# FE_Channel.net
KiCad netlist of a schematic drawn in Altium Designer
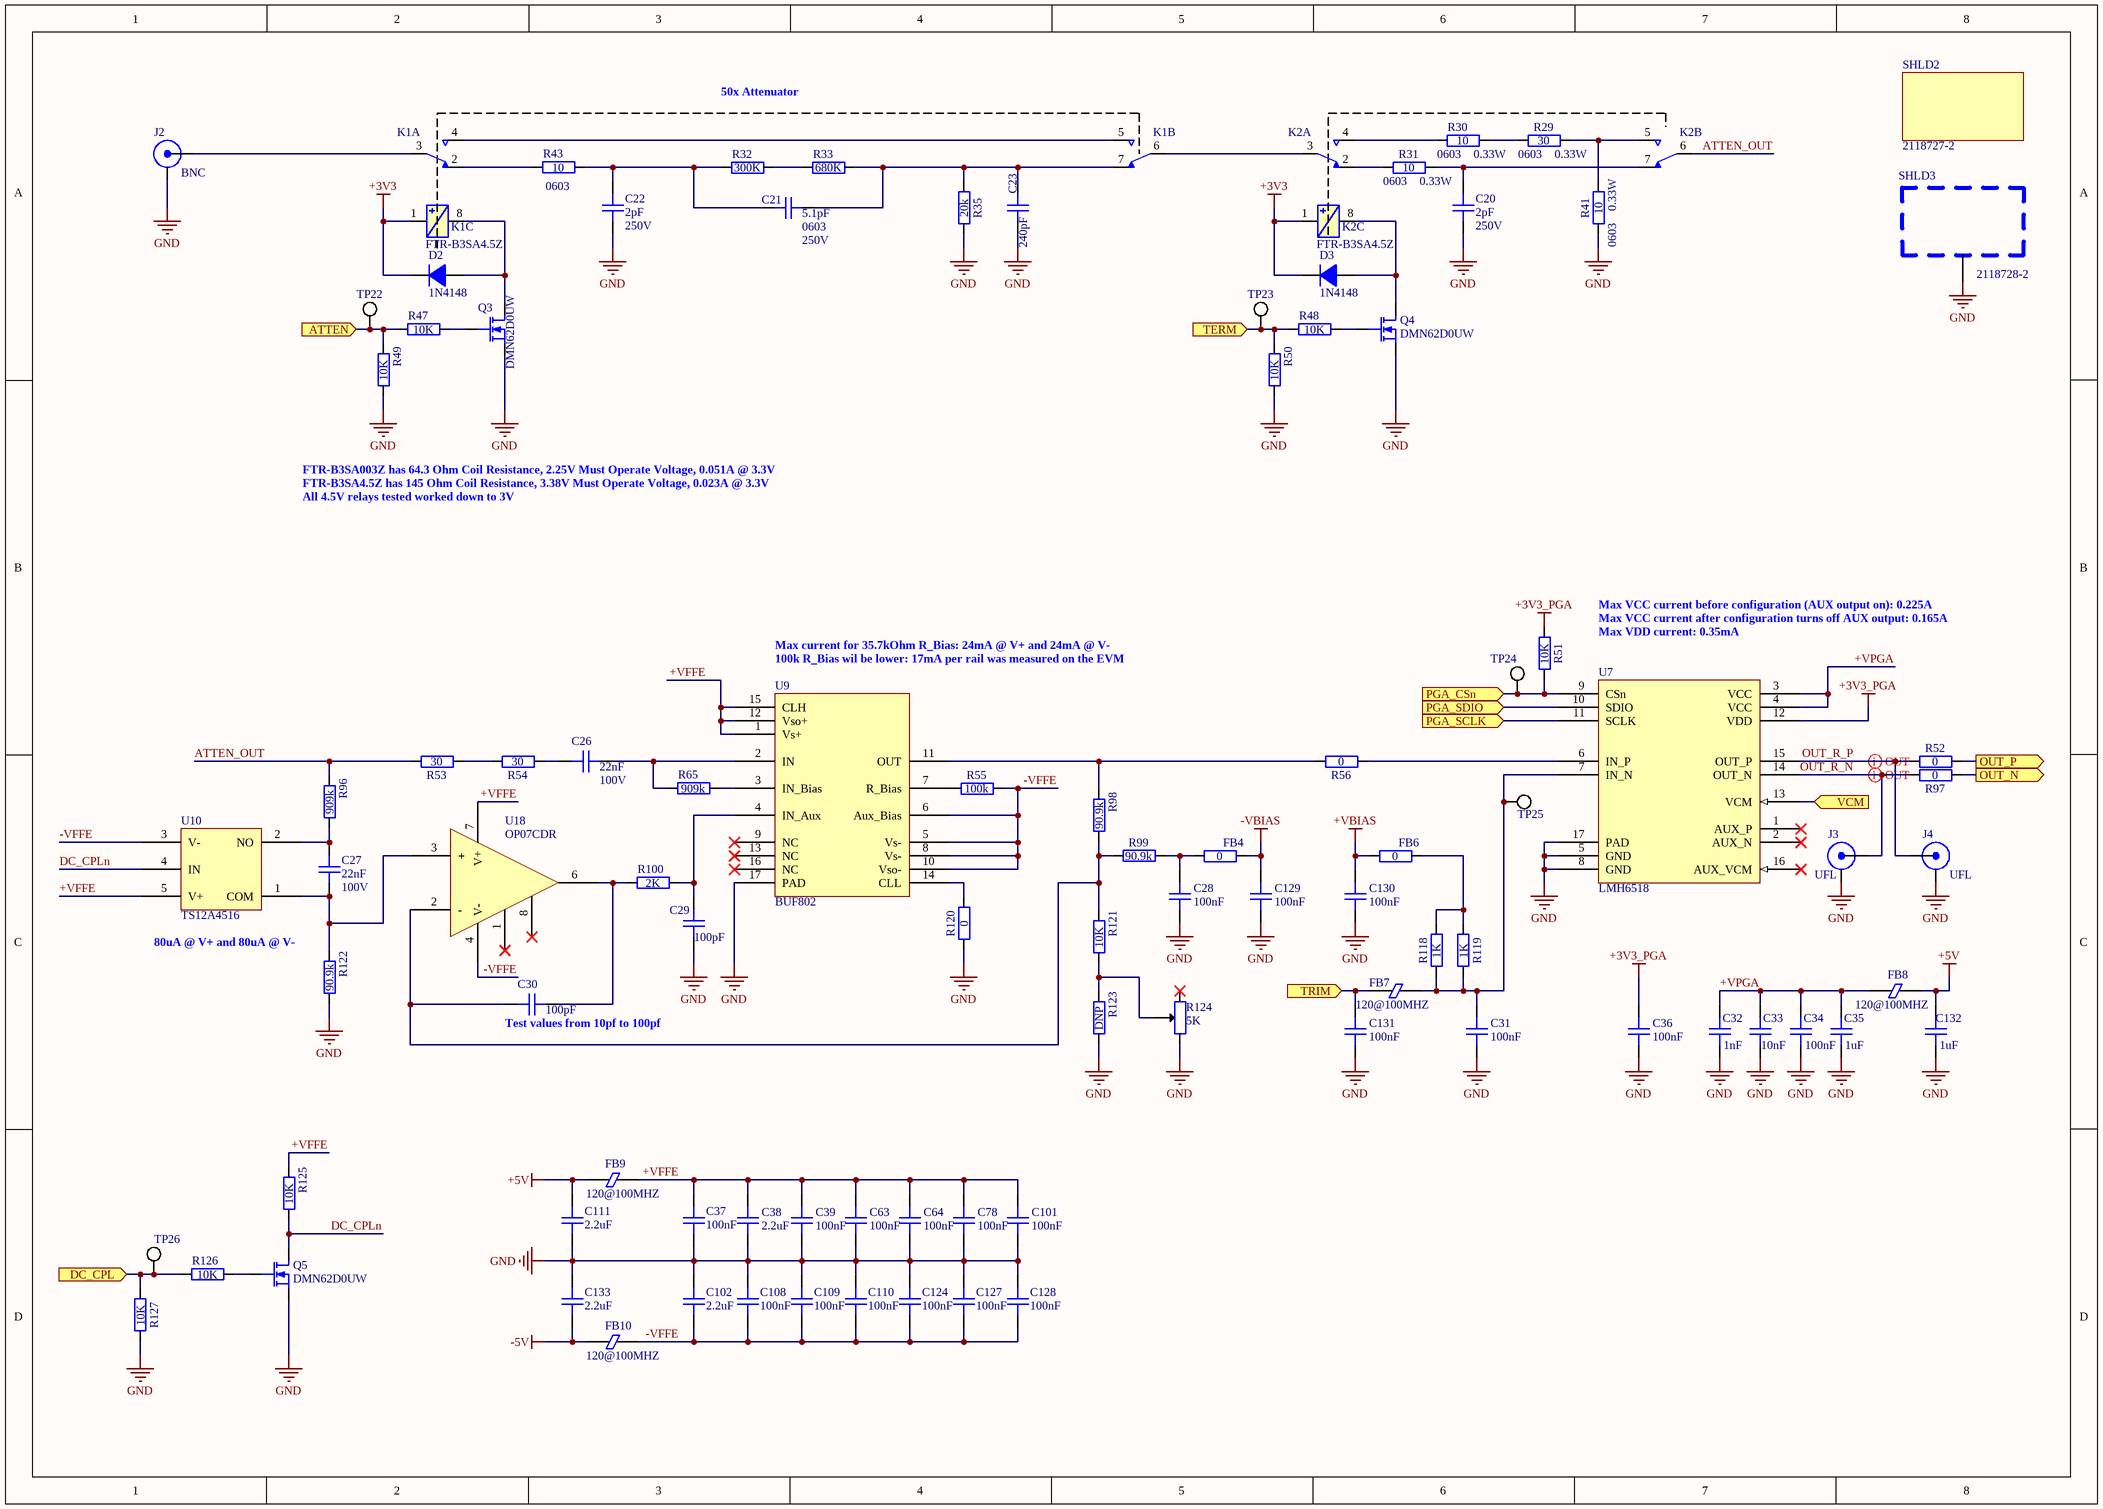
[diagram p0: FE_Channel.SchDoc]

(export (version "E")
  (design (tool "Eeschema 10.0.6"))
  (components
    (comp (ref "C20")
      (value "2pF")
      (footprint "GEN_C_0603")
      (fields
        (field (name "MANUFACTURER") "KEMET")
        (field (name "MANUFACTURER PART NUMBER") "CBR06C309BAGAC")
        (field (name "VOLTAGE RATING") "250V")
      )
      (libsource (lib "DSO") (part "CAP 2pF 250V C0G 0603"))
    )
    (comp (ref "C21")
      (value "5.1pF")
      (footprint "GEN_C_0603")
      (fields
        (field (name "PACKAGE") "0603")
        (field (name "VOLTAGE RATING") "250V")
        (field (name "MANUFACTURER") "KEMET")
        (field (name "MANUFACTURER PART NUMBER") "CBR06C519BAGAC")
      )
      (libsource (lib "DSO") (part "CAP 5.1pF 250V C0G 0603"))
    )
    (comp (ref "C22")
      (value "2pF")
      (footprint "GEN_C_0603")
      (fields
        (field (name "MANUFACTURER") "KEMET")
        (field (name "MANUFACTURER PART NUMBER") "CBR06C309BAGAC")
        (field (name "VOLTAGE RATING") "250V")
      )
      (libsource (lib "DSO") (part "CAP 2pF 250V C0G 0603"))
    )
    (comp (ref "C23")
      (value "240pF")
      (footprint "GEN_C_0805")
      (fields
        (field (name "MANUFACTURER") "Kyocera AVX")
        (field (name "MANUFACTURER PART NUMBER") "600F241FT250XT")
      )
      (libsource (lib "DSO") (part "CAP 240pF 250V C0G 0805"))
    )
    (comp (ref "C26")
      (value "22nF")
      (footprint "GEN_C_0603")
      (fields (field (name "VOLTAGE RATING") "100V"))
      (libsource (lib "DSO") (part "CAP 22nF 100V X7R 0603"))
    )
    (comp (ref "C27")
      (value "22nF")
      (footprint "GEN_C_0603")
      (fields (field (name "VOLTAGE RATING") "100V"))
      (libsource (lib "DSO") (part "CAP 22nF 100V X7R 0603"))
    )
    (comp (ref "C28")
      (value "100nF")
      (footprint "GEN_C_0402")
      (libsource (lib "DSO") (part "CAP 100nF 16V X7R 0402"))
    )
    (comp (ref "C29")
      (value "100pF")
      (footprint "GEN_C_0402")
      (libsource (lib "DSO") (part "CAP 100pF 50V C0G 0402"))
    )
    (comp (ref "C30")
      (value "100pF")
      (footprint "GEN_C_0402")
      (libsource (lib "DSO") (part "CAP 100pF 50V C0G 0402"))
    )
    (comp (ref "C31")
      (value "100nF")
      (footprint "GEN_C_0402")
      (libsource (lib "DSO") (part "CAP 100nF 16V X7R 0402"))
    )
    (comp (ref "C32")
      (value "1nF")
      (footprint "GEN_C_0402")
      (libsource (lib "DSO") (part "CAP 1nF 50V C0G 0402"))
    )
    (comp (ref "C33")
      (value "10nF")
      (footprint "GEN_C_0402")
      (libsource (lib "DSO") (part "CAP 10nF 50V X7R 0402"))
    )
    (comp (ref "C34")
      (value "100nF")
      (footprint "GEN_C_0402")
      (libsource (lib "DSO") (part "CAP 100nF 16V X7R 0402"))
    )
    (comp (ref "C35")
      (value "1uF")
      (footprint "GEN_C_0402")
      (libsource (lib "DSO") (part "CAP 1uF 25V X5R 0402"))
    )
    (comp (ref "C36")
      (value "100nF")
      (footprint "GEN_C_0402")
      (libsource (lib "DSO") (part "CAP 100nF 16V X7R 0402"))
    )
    (comp (ref "C37")
      (value "100nF")
      (footprint "GEN_C_0402")
      (fields
        (field (name "MANUFACTURER") "Murata")
        (field (name "HOUSE PART NUMBER") "C-100nF-0402-002")
        (field (name "MANUFACTURER PART NUMBER") "GCM155R71C104KA55D")
      )
      (libsource (lib "DSO") (part "CAP 100nF 16V X7R 0402"))
    )
    (comp (ref "C38")
      (value "2.2uF")
      (footprint "GEN_C_0402")
      (fields
        (field (name "MANUFACTURER") "Taiyo Yuden")
        (field (name "MANUFACTURER PART NUMBER") "LMK105BJ225MV-F")
      )
      (libsource (lib "DSO") (part "CAP 2.2uF 10V X5R 0402"))
    )
    (comp (ref "C39")
      (value "100nF")
      (footprint "GEN_C_0402")
      (libsource (lib "DSO") (part "CAP 100nF 16V X7R 0402"))
    )
    (comp (ref "C63")
      (value "100nF")
      (footprint "GEN_C_0402")
      (libsource (lib "DSO") (part "CAP 100nF 16V X7R 0402"))
    )
    (comp (ref "C64")
      (value "100nF")
      (footprint "GEN_C_0402")
      (libsource (lib "DSO") (part "CAP 100nF 16V X7R 0402"))
    )
    (comp (ref "C78")
      (value "100nF")
      (footprint "GEN_C_0402")
      (libsource (lib "DSO") (part "CAP 100nF 16V X7R 0402"))
    )
    (comp (ref "C101")
      (value "100nF")
      (footprint "GEN_C_0402")
      (libsource (lib "DSO") (part "CAP 100nF 16V X7R 0402"))
    )
    (comp (ref "C102")
      (value "2.2uF")
      (footprint "GEN_C_0402")
      (libsource (lib "DSO") (part "CAP 2.2uF 10V X5R 0402"))
    )
    (comp (ref "C108")
      (value "100nF")
      (footprint "GEN_C_0402")
      (libsource (lib "DSO") (part "CAP 100nF 16V X7R 0402"))
    )
    (comp (ref "C109")
      (value "100nF")
      (footprint "GEN_C_0402")
      (libsource (lib "DSO") (part "CAP 100nF 16V X7R 0402"))
    )
    (comp (ref "C110")
      (value "100nF")
      (footprint "GEN_C_0402")
      (libsource (lib "DSO") (part "CAP 100nF 16V X7R 0402"))
    )
    (comp (ref "C111")
      (value "2.2uF")
      (footprint "GEN_C_0402")
      (libsource (lib "DSO") (part "CAP 2.2uF 10V X5R 0402"))
    )
    (comp (ref "C124")
      (value "100nF")
      (footprint "GEN_C_0402")
      (libsource (lib "DSO") (part "CAP 100nF 16V X7R 0402"))
    )
    (comp (ref "C127")
      (value "100nF")
      (footprint "GEN_C_0402")
      (libsource (lib "DSO") (part "CAP 100nF 16V X7R 0402"))
    )
    (comp (ref "C128")
      (value "100nF")
      (footprint "GEN_C_0402")
      (libsource (lib "DSO") (part "CAP 100nF 16V X7R 0402"))
    )
    (comp (ref "C129")
      (value "100nF")
      (footprint "GEN_C_0402")
      (libsource (lib "DSO") (part "CAP 100nF 16V X7R 0402"))
    )
    (comp (ref "C130")
      (value "100nF")
      (footprint "GEN_C_0402")
      (libsource (lib "DSO") (part "CAP 100nF 16V X7R 0402"))
    )
    (comp (ref "C131")
      (value "100nF")
      (footprint "GEN_C_0402")
      (libsource (lib "DSO") (part "CAP 100nF 16V X7R 0402"))
    )
    (comp (ref "C132")
      (value "1uF")
      (footprint "GEN_C_0402")
      (libsource (lib "DSO") (part "CAP 1uF 25V X5R 0402"))
    )
    (comp (ref "C133")
      (value "2.2uF")
      (footprint "GEN_C_0402")
      (libsource (lib "DSO") (part "CAP 2.2uF 10V X5R 0402"))
    )
    (comp (ref "D2") (value "1N4148") (footprint "GEN_SOD_323") (libsource (lib "DSO") (part "DIODE 1N4148")))
    (comp (ref "D3") (value "1N4148") (footprint "GEN_SOD_323") (libsource (lib "DSO") (part "DIODE 1N4148")))
    (comp (ref "FB4")
      (value "0")
      (footprint "GEN_R_0402")
      (fields
        (field (name "MANUFACTURER") "Yageo")
        (field (name "MANUFACTURER PART NUMBER") "RC0402JR-070RL")
      )
      (libsource (lib "DSO") (part "RES 0 OHM 1/16W 0402"))
    )
    (comp (ref "FB6")
      (value "0")
      (footprint "GEN_R_0402")
      (fields
        (field (name "MANUFACTURER") "Yageo")
        (field (name "MANUFACTURER PART NUMBER") "RC0402JR-070RL")
      )
      (libsource (lib "DSO") (part "RES 0 OHM 1/16W 0402"))
    )
    (comp (ref "FB7")
      (value "120@100MHZ")
      (footprint "GEN_R_0402")
      (libsource (lib "DSO") (part "FERRITE BEAD 120 OHM 0402"))
    )
    (comp (ref "FB8")
      (value "120@100MHZ")
      (footprint "GEN_R_0402")
      (libsource (lib "DSO") (part "FERRITE BEAD 120 OHM 0402"))
    )
    (comp (ref "FB9")
      (value "120@100MHZ")
      (footprint "GEN_R_0402")
      (libsource (lib "DSO") (part "FERRITE BEAD 120 OHM 0402"))
    )
    (comp (ref "FB10")
      (value "120@100MHZ")
      (footprint "GEN_R_0402")
      (libsource (lib "DSO") (part "FERRITE BEAD 120 OHM 0402"))
    )
    (comp (ref "J2") (value "BNC") (footprint "MOL_0731000105") (libsource (lib "DSO") (part "BNC JACK R/A")))
    (comp (ref "J3") (value "UFL") (footprint "TE_2334884-1") (libsource (lib "DSO") (part "UFL Jack SMD")))
    (comp (ref "J4") (value "UFL") (footprint "TE_2334884-1") (libsource (lib "DSO") (part "UFL Jack SMD")))
    (comp (ref "K1")
      (value "FTR-B3SA4.5Z")
      (footprint "FUJ_FTR-B3SA")
      (fields (field (name "MANUFACTURER") "Fujitsu"))
      (libsource (lib "") (part "RELAY DPDT-NO FTR-B3SA4.5Z_1"))
    )
    (comp (ref "K2")
      (value "FTR-B3SA4.5Z")
      (footprint "FUJ_FTR-B3SA")
      (fields (field (name "MANUFACTURER") "Fujitsu"))
      (libsource (lib "DSO") (part "RELAY DPDT-NO FTR-B3SA4.5Z"))
    )
    (comp (ref "Q3")
      (value "DMN62D0UW")
      (footprint "GEN_SOT_323")
      (libsource (lib "DSO") (part "NMOS DMN62D0UW"))
    )
    (comp (ref "Q4")
      (value "DMN62D0UW")
      (footprint "GEN_SOT_323")
      (libsource (lib "DSO") (part "NMOS DMN62D0UW"))
    )
    (comp (ref "Q5")
      (value "DMN62D0UW")
      (footprint "GEN_SOT_323")
      (libsource (lib "DSO") (part "NMOS DMN62D0UW"))
    )
    (comp (ref "R29")
      (value "30")
      (footprint "GEN_R_0603")
      (fields
        (field (name "TOLERANCE") "1%")
        (field (name "POWER RATING") "0.33W")
        (field (name "PACKAGE") "0603")
      )
      (libsource (lib "DSO") (part "RES 30 OHM 1% 1/3W 0603"))
    )
    (comp (ref "R30")
      (value "10")
      (footprint "GEN_R_0603")
      (fields
        (field (name "PACKAGE") "0603")
        (field (name "TOLERANCE") "1%")
        (field (name "POWER RATING") "0.33W")
      )
      (libsource (lib "DSO") (part "RES 10 OHM 1% 1/3W 0603"))
    )
    (comp (ref "R31")
      (value "10")
      (footprint "GEN_R_0603")
      (fields
        (field (name "TOLERANCE") "1%")
        (field (name "PACKAGE") "0603")
        (field (name "MANUFACTURER") "KOA Speer")
        (field (name "MANUFACTURER PART NUMBER") "SG73P1JTTD10R0F")
        (field (name "POWER RATING") "0.33W")
      )
      (libsource (lib "DSO") (part "RES 10 OHM 1% 1/3W 0603"))
    )
    (comp (ref "R32")
      (value "300K")
      (footprint "GEN_R_0402")
      (fields
        (field (name "TOLERANCE") "1%")
        (field (name "MANUFACTURER") "Panasonic")
        (field (name "MANUFACTURER PART NUMBER") "ERJ-2RKF3003X")
      )
      (libsource (lib "DSO") (part "RES 300K OHM 1% 1/10W 0402"))
    )
    (comp (ref "R33")
      (value "680K")
      (footprint "GEN_R_0402")
      (fields
        (field (name "TOLERANCE") "1%")
        (field (name "MANUFACTURER") "Yageo")
        (field (name "MANUFACTURER PART NUMBER") "RC0402FR-07681KL")
      )
      (libsource (lib "DSO") (part "RES 680K OHM 1% 1/16W 0402"))
    )
    (comp (ref "R35")
      (value "20k")
      (footprint "GEN_R_0402")
      (fields
        (field (name "TOLERANCE") "1%")
        (field (name "MANUFACTURER") "Yageo")
        (field (name "MANUFACTURER PART NUMBER") "RC0402FR-0720KL")
      )
      (libsource (lib "DSO") (part "RES 20K OHM 1% 1/16W 0402"))
    )
    (comp (ref "R41")
      (value "10")
      (footprint "GEN_R_0603")
      (fields
        (field (name "TOLERANCE") "1%")
        (field (name "POWER RATING") "0.33W")
        (field (name "PACKAGE") "0603")
      )
      (libsource (lib "") (part "RES 10 OHM 1% 1/3W 0603_2"))
    )
    (comp (ref "R43")
      (value "10")
      (footprint "GEN_R_0603")
      (fields
        (field (name "TOLERANCE") "1%")
        (field (name "PACKAGE") "0603")
        (field (name "MANUFACTURER") "KOA Speer")
        (field (name "MANUFACTURER PART NUMBER") "SG73P1JTTD10R0F")
      )
      (libsource (lib "") (part "RES 10 OHM 1% 1/3W 0603_1"))
    )
    (comp (ref "R47")
      (value "10K")
      (footprint "GEN_R_0402")
      (fields (field (name "TOLERANCE") "1%"))
      (libsource (lib "") (part "RES 10K OHM 1% 1/10W 0402_1"))
    )
    (comp (ref "R48")
      (value "10K")
      (footprint "GEN_R_0402")
      (fields (field (name "TOLERANCE") "1%"))
      (libsource (lib "") (part "RES 10K OHM 1% 1/10W 0402_1"))
    )
    (comp (ref "R49")
      (value "10K")
      (footprint "GEN_R_0402")
      (fields (field (name "TOLERANCE") "1%"))
      (libsource (lib "DSO") (part "RES 10K OHM 1% 1/10W 0402"))
    )
    (comp (ref "R50")
      (value "10K")
      (footprint "GEN_R_0402")
      (fields (field (name "TOLERANCE") "1%"))
      (libsource (lib "DSO") (part "RES 10K OHM 1% 1/10W 0402"))
    )
    (comp (ref "R51")
      (value "10K")
      (footprint "GEN_R_0402")
      (fields (field (name "TOLERANCE") "1%"))
      (libsource (lib "DSO") (part "RES 10K OHM 1% 1/10W 0402"))
    )
    (comp (ref "R52")
      (value "0")
      (footprint "GEN_R_0402")
      (libsource (lib "DSO") (part "RES 0 OHM 1/16W 0402"))
    )
    (comp (ref "R53")
      (value "30")
      (footprint "GEN_R_0603")
      (fields
        (field (name "TOLERANCE") "1%")
        (field (name "MANUFACTURER") "KOA Speer")
        (field (name "MANUFACTURER PART NUMBER") "SG73P1JTTD30R0F")
      )
      (libsource (lib "DSO") (part "RES 30 OHM 1% 1/3W 0603"))
    )
    (comp (ref "R54")
      (value "30")
      (footprint "GEN_R_0603")
      (fields
        (field (name "TOLERANCE") "1%")
        (field (name "MANUFACTURER") "KOA Speer")
        (field (name "MANUFACTURER PART NUMBER") "SG73P1JTTD30R0F")
      )
      (libsource (lib "DSO") (part "RES 30 OHM 1% 1/3W 0603"))
    )
    (comp (ref "R55")
      (value "100k")
      (footprint "GEN_R_0402")
      (fields (field (name "TOLERANCE") "1%"))
      (libsource (lib "DSO") (part "RES 100K OHM 1% 1/10W 0402"))
    )
    (comp (ref "R56")
      (value "0")
      (footprint "GEN_R_0402")
      (fields
        (field (name "MANUFACTURER") "Yageo")
        (field (name "MANUFACTURER PART NUMBER") "RC0402JR-070RL")
      )
      (libsource (lib "DSO") (part "RES 0 OHM 1/16W 0402"))
    )
    (comp (ref "R65")
      (value "909k")
      (footprint "GEN_R_0402")
      (fields (field (name "TOLERANCE") "1%"))
      (libsource (lib "") (part "RES 909K OHM 1% 1/16W 0402_1"))
    )
    (comp (ref "R96")
      (value "909k")
      (footprint "GEN_R_0402")
      (fields (field (name "TOLERANCE") "1%"))
      (libsource (lib "DSO") (part "RES 909K OHM 1% 1/16W 0402"))
    )
    (comp (ref "R97")
      (value "0")
      (footprint "GEN_R_0402")
      (libsource (lib "DSO") (part "RES 0 OHM 1/16W 0402"))
    )
    (comp (ref "R98")
      (value "90.9k")
      (footprint "GEN_R_0402")
      (fields (field (name "TOLERANCE") "1%"))
      (libsource (lib "DSO") (part "RES 90.9K OHM 1% 1/16W 0402"))
    )
    (comp (ref "R99")
      (value "90.9k")
      (footprint "GEN_R_0402")
      (fields (field (name "TOLERANCE") "1%"))
      (libsource (lib "") (part "RES 90.9K OHM 1% 1/16W 0402_1"))
    )
    (comp (ref "R100")
      (value "2K")
      (footprint "GEN_R_0402")
      (fields (field (name "TOLERANCE") "1%"))
      (libsource (lib "DSO") (part "RES 2K OHM 1% 1/16W 0402"))
    )
    (comp (ref "R118")
      (value "1K")
      (footprint "GEN_R_0402")
      (fields (field (name "TOLERANCE") "1%"))
      (libsource (lib "") (part "RES 1K OHM 1% 1/10W 0402_1"))
    )
    (comp (ref "R119")
      (value "1K")
      (footprint "GEN_R_0402")
      (fields (field (name "TOLERANCE") "1%"))
      (libsource (lib "DSO") (part "RES 1K OHM 1% 1/10W 0402"))
    )
    (comp (ref "R120")
      (value "0")
      (footprint "GEN_R_0402")
      (libsource (lib "") (part "RES 0 OHM 1/16W 0402_1"))
    )
    (comp (ref "R121")
      (value "10K")
      (footprint "GEN_R_0402")
      (fields (field (name "TOLERANCE") "1%"))
      (libsource (lib "DSO") (part "RES 10K OHM 1% 1/10W 0402"))
    )
    (comp (ref "R122")
      (value "90.9k")
      (footprint "GEN_R_0402")
      (fields (field (name "TOLERANCE") "1%"))
      (libsource (lib "DSO") (part "RES 90.9K OHM 1% 1/16W 0402"))
    )
    (comp (ref "R123")
      (value "DNP")
      (footprint "GEN_R_0402")
      (fields (field (name "TOLERANCE") "1%"))
      (libsource (lib "DSO") (part "RES DNP 0402"))
    )
    (comp (ref "R124")
      (value "5K")
      (footprint "BOU_3mm_POT")
      (fields (field (name "TOLERANCE") "1%"))
      (libsource (lib "DSO") (part "TRIMMER 5K OHM 0.1W J LEAD TOP"))
    )
    (comp (ref "R125")
      (value "10K")
      (footprint "GEN_R_0402")
      (fields
        (field (name "TOLERANCE") "1%")
        (field (name "MANUFACTURER") "Panasonic")
        (field (name "MANUFACTURER PART NUMBER") "ERJ-2RKF1002X")
      )
      (libsource (lib "DSO") (part "RES 10K OHM 1% 1/10W 0402"))
    )
    (comp (ref "R126")
      (value "10K")
      (footprint "GEN_R_0402")
      (fields (field (name "TOLERANCE") "1%"))
      (libsource (lib "") (part "RES 10K OHM 1% 1/10W 0402_1"))
    )
    (comp (ref "R127")
      (value "10K")
      (footprint "GEN_R_0402")
      (fields
        (field (name "TOLERANCE") "1%")
        (field (name "MANUFACTURER") "Panasonic")
        (field (name "MANUFACTURER PART NUMBER") "ERJ-2RKF1002X")
      )
      (libsource (lib "") (part "RES 10K OHM 1% 1/10W 0402_2"))
    )
    (comp (ref "SHLD2") (value "2118727-2") (libsource (lib "DSO") (part "SHIELD 2118727-2")))
    (comp (ref "SHLD3")
      (value "2118728-2")
      (footprint "TE_2118728-2")
      (libsource (lib "DSO") (part "SHIELD 2118728-2"))
    )
    (comp (ref "TP22") (value "PCB") (footprint "GEN_TP_PCB") (libsource (lib "DSO") (part "TP PCB 1mm")))
    (comp (ref "TP23") (value "PCB") (footprint "GEN_TP_PCB") (libsource (lib "DSO") (part "TP PCB 1mm")))
    (comp (ref "TP24") (value "PCB") (footprint "GEN_TP_PCB") (libsource (lib "DSO") (part "TP PCB 1mm")))
    (comp (ref "TP25") (value "PCB") (footprint "GEN_TP_PCB") (libsource (lib "DSO") (part "TP PCB 1mm")))
    (comp (ref "TP26") (value "PCB") (footprint "GEN_TP_PCB") (libsource (lib "DSO") (part "TP PCB 1mm")))
    (comp (ref "U7")
      (value "LMH6518")
      (footprint "TI_WQFN_RGH0016A")
      (libsource (lib "DSO") (part "IC PGA LMH6518"))
    )
    (comp (ref "U9")
      (value "BUF802")
      (footprint "TI_VQFN_RGT0016C")
      (libsource (lib "DSO") (part "IC BUFFER AMP BUF802"))
    )
    (comp (ref "U10")
      (value "TS12A4516")
      (footprint "GEN_SOT23_5_950_2900X1600X1450")
      (fields
        (field (name "MANUFACTURER") "Texas Instruments")
        (field (name "MANUFACTURER PART NUMBER") "TS12A4516DBVR")
      )
      (libsource (lib "DSO") (part "IC SWITCH SPST TS12A4516DBVR"))
    )
    (comp (ref "U18")
      (value "OP07CDR")
      (footprint "TI_SOIC8_D0008A")
      (libsource (lib "DSO") (part "IC OPAMP OP07CDR"))
    )
  )
  (nets
    (net (code "1") (name "+3V3") (class "Default")
      (node (ref "D2") (pin "1") (pinfunction "K_1") (pintype "passive"))
      (node (ref "D3") (pin "1") (pinfunction "K_1") (pintype "passive"))
      (node (ref "K1") (pin "1") (pinfunction "1_1") (pintype "passive"))
      (node (ref "K2") (pin "1") (pinfunction "1_1") (pintype "passive"))
    )
    (net (code "2") (name "+3V3_PGA") (class "Default")
      (node (ref "C36") (pin "2") (pinfunction "2_2") (pintype "passive"))
      (node (ref "R51") (pin "2") (pinfunction "2_2") (pintype "passive"))
      (node (ref "U7") (pin "12") (pinfunction "VDD_12") (pintype "power_in"))
    )
    (net (code "3") (name "+5V") (class "Default")
      (node (ref "C111") (pin "2") (pinfunction "2_2") (pintype "passive"))
      (node (ref "C132") (pin "2") (pinfunction "2_2") (pintype "passive"))
      (node (ref "FB8") (pin "2") (pinfunction "2_2") (pintype "passive"))
      (node (ref "FB9") (pin "1") (pinfunction "1_1") (pintype "passive"))
    )
    (net (code "4") (name "+VBIAS") (class "Default")
      (node (ref "C130") (pin "1") (pinfunction "1_1") (pintype "passive"))
      (node (ref "FB6") (pin "1") (pinfunction "1_1") (pintype "passive"))
    )
    (net (code "5") (name "-5V") (class "Default")
      (node (ref "C133") (pin "1") (pinfunction "1_1") (pintype "passive"))
      (node (ref "FB10") (pin "1") (pinfunction "1_1") (pintype "passive"))
    )
    (net (code "6") (name "-VBIAS") (class "Default")
      (node (ref "C129") (pin "1") (pinfunction "1_1") (pintype "passive"))
      (node (ref "FB4") (pin "2") (pinfunction "2_2") (pintype "passive"))
    )
    (net (code "7") (name "/+VFFE") (class "Default")
      (node (ref "C101") (pin "2") (pinfunction "2_2") (pintype "passive"))
      (node (ref "C37") (pin "2") (pinfunction "2_2") (pintype "passive"))
      (node (ref "C38") (pin "1") (pinfunction "1_1") (pintype "passive"))
      (node (ref "C39") (pin "1") (pinfunction "1_1") (pintype "passive"))
      (node (ref "C63") (pin "1") (pinfunction "1_1") (pintype "passive"))
      (node (ref "C64") (pin "2") (pinfunction "2_2") (pintype "passive"))
      (node (ref "C78") (pin "2") (pinfunction "2_2") (pintype "passive"))
      (node (ref "FB9") (pin "2") (pinfunction "2_2") (pintype "passive"))
      (node (ref "R125") (pin "2") (pinfunction "2_2") (pintype "passive"))
      (node (ref "U10") (pin "5") (pinfunction "V+_5") (pintype "passive"))
      (node (ref "U18") (pin "7") (pinfunction "V+_7") (pintype "passive"))
      (node (ref "U9") (pin "1") (pinfunction "Vs+_1") (pintype "passive"))
      (node (ref "U9") (pin "12") (pinfunction "Vso+_12") (pintype "passive"))
      (node (ref "U9") (pin "15") (pinfunction "CLH_15") (pintype "passive"))
    )
    (net (code "8") (name "/+VPGA") (class "Default")
      (node (ref "C32") (pin "2") (pinfunction "2_2") (pintype "passive"))
      (node (ref "C33") (pin "2") (pinfunction "2_2") (pintype "passive"))
      (node (ref "C34") (pin "2") (pinfunction "2_2") (pintype "passive"))
      (node (ref "C35") (pin "2") (pinfunction "2_2") (pintype "passive"))
      (node (ref "FB8") (pin "1") (pinfunction "1_1") (pintype "passive"))
      (node (ref "U7") (pin "3") (pinfunction "VCC_3") (pintype "power_in"))
      (node (ref "U7") (pin "4") (pinfunction "VCC_4") (pintype "power_in"))
    )
    (net (code "9") (name "/-VFFE") (class "Default")
      (node (ref "C102") (pin "2") (pinfunction "2_2") (pintype "passive"))
      (node (ref "C108") (pin "2") (pinfunction "2_2") (pintype "passive"))
      (node (ref "C109") (pin "1") (pinfunction "1_1") (pintype "passive"))
      (node (ref "C110") (pin "1") (pinfunction "1_1") (pintype "passive"))
      (node (ref "C124") (pin "1") (pinfunction "1_1") (pintype "passive"))
      (node (ref "C127") (pin "2") (pinfunction "2_2") (pintype "passive"))
      (node (ref "C128") (pin "2") (pinfunction "2_2") (pintype "passive"))
      (node (ref "FB10") (pin "2") (pinfunction "2_2") (pintype "passive"))
      (node (ref "R55") (pin "2") (pinfunction "2_2") (pintype "passive"))
      (node (ref "U10") (pin "3") (pinfunction "V-_3") (pintype "passive"))
      (node (ref "U18") (pin "4") (pinfunction "V-_4") (pintype "passive"))
      (node (ref "U9") (pin "10") (pinfunction "Vso-_10") (pintype "passive"))
      (node (ref "U9") (pin "5") (pinfunction "Vs-_5") (pintype "passive"))
      (node (ref "U9") (pin "6") (pinfunction "Aux_Bias_6") (pintype "passive"))
      (node (ref "U9") (pin "8") (pinfunction "Vs-_8") (pintype "passive"))
    )
    (net (code "10") (name "/ATTEN") (class "Default")
      (node (ref "R47") (pin "2") (pinfunction "2_2") (pintype "passive"))
      (node (ref "R49") (pin "2") (pinfunction "2_2") (pintype "passive"))
      (node (ref "TP22") (pin "1") (pinfunction "1_1") (pintype "passive"))
    )
    (net (code "11") (name "/ATTEN_OUT") (class "Default")
      (node (ref "K2") (pin "6") (pinfunction "6_6") (pintype "passive"))
      (node (ref "R53") (pin "1") (pinfunction "1_1") (pintype "passive"))
      (node (ref "R96") (pin "2") (pinfunction "2_2") (pintype "passive"))
    )
    (net (code "12") (name "/DC_CPL") (class "Default")
      (node (ref "R126") (pin "2") (pinfunction "2_2") (pintype "passive"))
      (node (ref "R127") (pin "2") (pinfunction "2_2") (pintype "passive"))
      (node (ref "TP26") (pin "1") (pinfunction "1_1") (pintype "passive"))
    )
    (net (code "13") (name "/DC_CPLn") (class "Default")
      (node (ref "Q5") (pin "1") (pinfunction "D_1") (pintype "passive"))
      (node (ref "R125") (pin "1") (pinfunction "1_1") (pintype "passive"))
      (node (ref "U10") (pin "4") (pinfunction "IN_4") (pintype "passive"))
    )
    (net (code "14") (name "/OUT_N") (class "Default")
      (node (ref "R97") (pin "2") (pinfunction "2_2") (pintype "passive"))
    )
    (net (code "15") (name "/OUT_P") (class "Default")
      (node (ref "R52") (pin "2") (pinfunction "2_2") (pintype "passive"))
    )
    (net (code "16") (name "/OUT_R_N") (class "Default")
      (node (ref "J3") (pin "1") (pinfunction "Signal_1") (pintype "passive"))
      (node (ref "R97") (pin "1") (pinfunction "1_1") (pintype "passive"))
      (node (ref "U7") (pin "14") (pinfunction "OUT_N_14") (pintype "passive"))
    )
    (net (code "17") (name "/OUT_R_P") (class "Default")
      (node (ref "J4") (pin "1") (pinfunction "Signal_1") (pintype "passive"))
      (node (ref "R52") (pin "1") (pinfunction "1_1") (pintype "passive"))
      (node (ref "U7") (pin "15") (pinfunction "OUT_P_15") (pintype "passive"))
    )
    (net (code "18") (name "/PGA_CSn") (class "Default")
      (node (ref "R51") (pin "1") (pinfunction "1_1") (pintype "passive"))
      (node (ref "TP24") (pin "1") (pinfunction "1_1") (pintype "passive"))
      (node (ref "U7") (pin "9") (pinfunction "CSn_9") (pintype "passive"))
    )
    (net (code "19") (name "/PGA_SCLK") (class "Default")
      (node (ref "U7") (pin "11") (pinfunction "SCLK_11") (pintype "passive"))
    )
    (net (code "20") (name "/PGA_SDIO") (class "Default")
      (node (ref "U7") (pin "10") (pinfunction "SDIO_10") (pintype "passive"))
    )
    (net (code "21") (name "/TERM") (class "Default")
      (node (ref "R48") (pin "2") (pinfunction "2_2") (pintype "passive"))
      (node (ref "R50") (pin "2") (pinfunction "2_2") (pintype "passive"))
      (node (ref "TP23") (pin "1") (pinfunction "1_1") (pintype "passive"))
    )
    (net (code "22") (name "/TRIM") (class "Default")
      (node (ref "C131") (pin "1") (pinfunction "1_1") (pintype "passive"))
      (node (ref "FB7") (pin "1") (pinfunction "1_1") (pintype "passive"))
    )
    (net (code "23") (name "/VCM") (class "Default")
      (node (ref "U7") (pin "13") (pinfunction "VCM_13") (pintype "input"))
    )
    (net (code "24") (name "GND") (class "Default")
      (node (ref "C101") (pin "1") (pinfunction "1_1") (pintype "passive"))
      (node (ref "C102") (pin "1") (pinfunction "1_1") (pintype "passive"))
      (node (ref "C108") (pin "1") (pinfunction "1_1") (pintype "passive"))
      (node (ref "C109") (pin "2") (pinfunction "2_2") (pintype "passive"))
      (node (ref "C110") (pin "2") (pinfunction "2_2") (pintype "passive"))
      (node (ref "C111") (pin "1") (pinfunction "1_1") (pintype "passive"))
      (node (ref "C124") (pin "2") (pinfunction "2_2") (pintype "passive"))
      (node (ref "C127") (pin "1") (pinfunction "1_1") (pintype "passive"))
      (node (ref "C128") (pin "1") (pinfunction "1_1") (pintype "passive"))
      (node (ref "C129") (pin "2") (pinfunction "2_2") (pintype "passive"))
      (node (ref "C130") (pin "2") (pinfunction "2_2") (pintype "passive"))
      (node (ref "C131") (pin "2") (pinfunction "2_2") (pintype "passive"))
      (node (ref "C132") (pin "1") (pinfunction "1_1") (pintype "passive"))
      (node (ref "C133") (pin "2") (pinfunction "2_2") (pintype "passive"))
      (node (ref "C20") (pin "2") (pinfunction "2_2") (pintype "passive"))
      (node (ref "C22") (pin "1") (pinfunction "1_1") (pintype "passive"))
      (node (ref "C23") (pin "1") (pinfunction "1_1") (pintype "passive"))
      (node (ref "C28") (pin "2") (pinfunction "2_2") (pintype "passive"))
      (node (ref "C29") (pin "1") (pinfunction "1_1") (pintype "passive"))
      (node (ref "C31") (pin "2") (pinfunction "2_2") (pintype "passive"))
      (node (ref "C32") (pin "1") (pinfunction "1_1") (pintype "passive"))
      (node (ref "C33") (pin "1") (pinfunction "1_1") (pintype "passive"))
      (node (ref "C34") (pin "1") (pinfunction "1_1") (pintype "passive"))
      (node (ref "C35") (pin "1") (pinfunction "1_1") (pintype "passive"))
      (node (ref "C36") (pin "1") (pinfunction "1_1") (pintype "passive"))
      (node (ref "C37") (pin "1") (pinfunction "1_1") (pintype "passive"))
      (node (ref "C38") (pin "2") (pinfunction "2_2") (pintype "passive"))
      (node (ref "C39") (pin "2") (pinfunction "2_2") (pintype "passive"))
      (node (ref "C63") (pin "2") (pinfunction "2_2") (pintype "passive"))
      (node (ref "C64") (pin "1") (pinfunction "1_1") (pintype "passive"))
      (node (ref "C78") (pin "1") (pinfunction "1_1") (pintype "passive"))
      (node (ref "J2") (pin "2") (pinfunction "SHIELD_2") (pintype "passive"))
      (node (ref "J3") (pin "2") (pinfunction "SHIELD_2") (pintype "passive"))
      (node (ref "J4") (pin "2") (pinfunction "SHIELD_2") (pintype "passive"))
      (node (ref "Q3") (pin "3") (pinfunction "S_3") (pintype "passive"))
      (node (ref "Q4") (pin "3") (pinfunction "S_3") (pintype "passive"))
      (node (ref "Q5") (pin "3") (pinfunction "S_3") (pintype "passive"))
      (node (ref "R120") (pin "1") (pinfunction "1_1") (pintype "passive"))
      (node (ref "R122") (pin "1") (pinfunction "1_1") (pintype "passive"))
      (node (ref "R123") (pin "1") (pinfunction "1_1") (pintype "passive"))
      (node (ref "R124") (pin "3") (pinfunction "3_3") (pintype "passive"))
      (node (ref "R127") (pin "1") (pinfunction "1_1") (pintype "passive"))
      (node (ref "R35") (pin "1") (pinfunction "1_1") (pintype "passive"))
      (node (ref "R41") (pin "1") (pinfunction "1_1") (pintype "passive"))
      (node (ref "R49") (pin "1") (pinfunction "1_1") (pintype "passive"))
      (node (ref "R50") (pin "1") (pinfunction "1_1") (pintype "passive"))
      (node (ref "SHLD3") (pin "1") (pinfunction "1_1") (pintype "passive"))
      (node (ref "U7") (pin "17") (pinfunction "PAD_17") (pintype "power_in"))
      (node (ref "U7") (pin "5") (pinfunction "GND_5") (pintype "power_in"))
      (node (ref "U7") (pin "8") (pinfunction "GND_8") (pintype "power_in"))
      (node (ref "U9") (pin "17") (pinfunction "PAD_17") (pintype "passive"))
    )
    (net (code "25") (name "Net-(C20-Pad1)") (class "Default")
      (node (ref "C20") (pin "1") (pinfunction "1_1") (pintype "passive"))
      (node (ref "K2") (pin "7") (pinfunction "7_7") (pintype "passive"))
      (node (ref "R31") (pin "2") (pinfunction "2_2") (pintype "passive"))
    )
    (net (code "26") (name "Net-(C21-Pad1)") (class "Default")
      (node (ref "C21") (pin "1") (pinfunction "1_1") (pintype "passive"))
      (node (ref "C23") (pin "2") (pinfunction "2_2") (pintype "passive"))
      (node (ref "K1") (pin "7") (pinfunction "7_7") (pintype "passive"))
      (node (ref "R33") (pin "2") (pinfunction "2_2") (pintype "passive"))
      (node (ref "R35") (pin "2") (pinfunction "2_2") (pintype "passive"))
    )
    (net (code "27") (name "Net-(C21-Pad2)") (class "Default")
      (node (ref "C21") (pin "2") (pinfunction "2_2") (pintype "passive"))
      (node (ref "C22") (pin "2") (pinfunction "2_2") (pintype "passive"))
      (node (ref "R32") (pin "1") (pinfunction "1_1") (pintype "passive"))
      (node (ref "R43") (pin "1") (pinfunction "1_1") (pintype "passive"))
    )
    (net (code "28") (name "Net-(C26-Pad2)") (class "Default")
      (node (ref "C26") (pin "2") (pinfunction "2_2") (pintype "passive"))
      (node (ref "R54") (pin "2") (pinfunction "2_2") (pintype "passive"))
    )
    (net (code "29") (name "Net-(C28-Pad1)") (class "Default")
      (node (ref "C28") (pin "1") (pinfunction "1_1") (pintype "passive"))
      (node (ref "FB4") (pin "1") (pinfunction "1_1") (pintype "passive"))
      (node (ref "R99") (pin "1") (pinfunction "1_1") (pintype "passive"))
    )
    (net (code "30") (name "Net-(D2-A)") (class "Default")
      (node (ref "D2") (pin "2") (pinfunction "A_2") (pintype "passive"))
      (node (ref "K1") (pin "8") (pinfunction "8_8") (pintype "passive"))
      (node (ref "Q3") (pin "1") (pinfunction "D_1") (pintype "passive"))
    )
    (net (code "31") (name "Net-(D3-A)") (class "Default")
      (node (ref "D3") (pin "2") (pinfunction "A_2") (pintype "passive"))
      (node (ref "K2") (pin "8") (pinfunction "8_8") (pintype "passive"))
      (node (ref "Q4") (pin "1") (pinfunction "D_1") (pintype "passive"))
    )
    (net (code "32") (name "Net-(FB6-Pad2)") (class "Default")
      (node (ref "FB6") (pin "2") (pinfunction "2_2") (pintype "passive"))
      (node (ref "R118") (pin "2") (pinfunction "2_2") (pintype "passive"))
      (node (ref "R119") (pin "1") (pinfunction "1_1") (pintype "passive"))
    )
    (net (code "33") (name "Net-(J2-Signal)") (class "Default")
      (node (ref "J2") (pin "1") (pinfunction "Signal_1") (pintype "passive"))
      (node (ref "K1") (pin "3") (pinfunction "3_3") (pintype "passive"))
    )
    (net (code "34") (name "Net-(K1-Pad2)") (class "Default")
      (node (ref "K1") (pin "2") (pinfunction "2_2") (pintype "passive"))
      (node (ref "R43") (pin "2") (pinfunction "2_2") (pintype "passive"))
    )
    (net (code "35") (name "Net-(K1-Pad4)") (class "Default")
      (node (ref "K1") (pin "4") (pinfunction "4_4") (pintype "passive"))
      (node (ref "K1") (pin "5") (pinfunction "5_5") (pintype "passive"))
    )
    (net (code "36") (name "Net-(K1-Pad6)") (class "Default")
      (node (ref "K1") (pin "6") (pinfunction "6_6") (pintype "passive"))
      (node (ref "K2") (pin "3") (pinfunction "3_3") (pintype "passive"))
    )
    (net (code "37") (name "Net-(K2-Pad2)") (class "Default")
      (node (ref "K2") (pin "2") (pinfunction "2_2") (pintype "passive"))
      (node (ref "R31") (pin "1") (pinfunction "1_1") (pintype "passive"))
    )
    (net (code "38") (name "Net-(K2-Pad4)") (class "Default")
      (node (ref "K2") (pin "4") (pinfunction "4_4") (pintype "passive"))
      (node (ref "R30") (pin "1") (pinfunction "1_1") (pintype "passive"))
    )
    (net (code "39") (name "Net-(K2-Pad5)") (class "Default")
      (node (ref "K2") (pin "5") (pinfunction "5_5") (pintype "passive"))
      (node (ref "R29") (pin "2") (pinfunction "2_2") (pintype "passive"))
      (node (ref "R41") (pin "2") (pinfunction "2_2") (pintype "passive"))
    )
    (net (code "40") (name "Net-(Q3-G)") (class "Default")
      (node (ref "Q3") (pin "2") (pinfunction "G_2") (pintype "passive"))
      (node (ref "R47") (pin "1") (pinfunction "1_1") (pintype "passive"))
    )
    (net (code "41") (name "Net-(Q4-G)") (class "Default")
      (node (ref "Q4") (pin "2") (pinfunction "G_2") (pintype "passive"))
      (node (ref "R48") (pin "1") (pinfunction "1_1") (pintype "passive"))
    )
    (net (code "42") (name "Net-(Q5-G)") (class "Default")
      (node (ref "Q5") (pin "2") (pinfunction "G_2") (pintype "passive"))
      (node (ref "R126") (pin "1") (pinfunction "1_1") (pintype "passive"))
    )
    (net (code "43") (name "Net-(R29-Pad1)") (class "Default")
      (node (ref "R29") (pin "1") (pinfunction "1_1") (pintype "passive"))
      (node (ref "R30") (pin "2") (pinfunction "2_2") (pintype "passive"))
    )
    (net (code "44") (name "Net-(R32-Pad2)") (class "Default")
      (node (ref "R32") (pin "2") (pinfunction "2_2") (pintype "passive"))
      (node (ref "R33") (pin "1") (pinfunction "1_1") (pintype "passive"))
    )
    (net (code "45") (name "Net-(R53-Pad2)") (class "Default")
      (node (ref "R53") (pin "2") (pinfunction "2_2") (pintype "passive"))
      (node (ref "R54") (pin "1") (pinfunction "1_1") (pintype "passive"))
    )
    (net (code "46") (name "Net-(R121-Pad1)") (class "Default")
      (node (ref "R121") (pin "1") (pinfunction "1_1") (pintype "passive"))
      (node (ref "R123") (pin "2") (pinfunction "2_2") (pintype "passive"))
      (node (ref "R124") (pin "2") (pinfunction "2_2") (pintype "passive"))
    )
    (net (code "47") (name "Net-(U7-IN_N)") (class "Default")
      (node (ref "C31") (pin "1") (pinfunction "1_1") (pintype "passive"))
      (node (ref "FB7") (pin "2") (pinfunction "2_2") (pintype "passive"))
      (node (ref "R118") (pin "1") (pinfunction "1_1") (pintype "passive"))
      (node (ref "R119") (pin "2") (pinfunction "2_2") (pintype "passive"))
      (node (ref "TP25") (pin "1") (pinfunction "1_1") (pintype "passive"))
      (node (ref "U7") (pin "7") (pinfunction "IN_N_7") (pintype "passive"))
    )
    (net (code "48") (name "Net-(U7-IN_P)") (class "Default")
      (node (ref "R56") (pin "2") (pinfunction "2_2") (pintype "passive"))
      (node (ref "U7") (pin "6") (pinfunction "IN_P_6") (pintype "passive"))
    )
    (net (code "49") (name "Net-(U9-CLL)") (class "Default")
      (node (ref "R120") (pin "2") (pinfunction "2_2") (pintype "passive"))
      (node (ref "U9") (pin "14") (pinfunction "CLL_14") (pintype "passive"))
    )
    (net (code "50") (name "Net-(U9-IN)") (class "Default")
      (node (ref "C26") (pin "1") (pinfunction "1_1") (pintype "passive"))
      (node (ref "R65") (pin "2") (pinfunction "2_2") (pintype "passive"))
      (node (ref "U9") (pin "2") (pinfunction "IN_2") (pintype "passive"))
    )
    (net (code "51") (name "Net-(U9-IN_Aux)") (class "Default")
      (node (ref "C29") (pin "2") (pinfunction "2_2") (pintype "passive"))
      (node (ref "R100") (pin "1") (pinfunction "1_1") (pintype "passive"))
      (node (ref "U9") (pin "4") (pinfunction "IN_Aux_4") (pintype "passive"))
    )
    (net (code "52") (name "Net-(U9-IN_Bias)") (class "Default")
      (node (ref "R65") (pin "1") (pinfunction "1_1") (pintype "passive"))
      (node (ref "U9") (pin "3") (pinfunction "IN_Bias_3") (pintype "passive"))
    )
    (net (code "53") (name "Net-(U9-OUT)") (class "Default")
      (node (ref "R56") (pin "1") (pinfunction "1_1") (pintype "passive"))
      (node (ref "R98") (pin "2") (pinfunction "2_2") (pintype "passive"))
      (node (ref "U9") (pin "11") (pinfunction "OUT_11") (pintype "passive"))
    )
    (net (code "54") (name "Net-(U9-R_Bias)") (class "Default")
      (node (ref "R55") (pin "1") (pinfunction "1_1") (pintype "passive"))
      (node (ref "U9") (pin "7") (pinfunction "R_Bias_7") (pintype "passive"))
    )
    (net (code "55") (name "Net-(U10-COM)") (class "Default")
      (node (ref "C27") (pin "2") (pinfunction "2_2") (pintype "passive"))
      (node (ref "R122") (pin "2") (pinfunction "2_2") (pintype "passive"))
      (node (ref "U10") (pin "1") (pinfunction "COM_1") (pintype "passive"))
      (node (ref "U18") (pin "3") (pinfunction "+_3") (pintype "passive"))
    )
    (net (code "56") (name "Net-(U10-NO)") (class "Default")
      (node (ref "C27") (pin "1") (pinfunction "1_1") (pintype "passive"))
      (node (ref "R96") (pin "1") (pinfunction "1_1") (pintype "passive"))
      (node (ref "U10") (pin "2") (pinfunction "NO_2") (pintype "passive"))
    )
    (net (code "57") (name "Net-(U18--)") (class "Default")
      (node (ref "C30") (pin "2") (pinfunction "2_2") (pintype "passive"))
      (node (ref "R121") (pin "2") (pinfunction "2_2") (pintype "passive"))
      (node (ref "R98") (pin "1") (pinfunction "1_1") (pintype "passive"))
      (node (ref "R99") (pin "2") (pinfunction "2_2") (pintype "passive"))
      (node (ref "U18") (pin "2") (pinfunction "-_2") (pintype "passive"))
    )
    (net (code "58") (name "Net-(U18-OUT)") (class "Default")
      (node (ref "C30") (pin "1") (pinfunction "1_1") (pintype "passive"))
      (node (ref "R100") (pin "2") (pinfunction "2_2") (pintype "passive"))
      (node (ref "U18") (pin "6") (pinfunction "OUT_6") (pintype "passive"))
    )
    (net (code "59") (name "unconnected-(R124-Pad1)") (class "Default")
      (node (ref "R124") (pin "1") (pinfunction "1_1") (pintype "passive+no_connect"))
    )
    (net (code "60") (name "unconnected-(U7-AUX_N-Pad2)") (class "Default")
      (node (ref "U7") (pin "2") (pinfunction "AUX_N_2") (pintype "passive+no_connect"))
    )
    (net (code "61") (name "unconnected-(U7-AUX_P-Pad1)") (class "Default")
      (node (ref "U7") (pin "1") (pinfunction "AUX_P_1") (pintype "passive+no_connect"))
    )
    (net (code "62") (name "unconnected-(U7-AUX_VCM-Pad16)") (class "Default")
      (node (ref "U7") (pin "16") (pinfunction "AUX_VCM_16") (pintype "input+no_connect"))
    )
    (net (code "63") (name "unconnected-(U9-NC-Pad9)") (class "Default")
      (node (ref "U9") (pin "9") (pinfunction "NC_9") (pintype "passive+no_connect"))
    )
    (net (code "64") (name "unconnected-(U9-NC-Pad13)") (class "Default")
      (node (ref "U9") (pin "13") (pinfunction "NC_13") (pintype "passive+no_connect"))
    )
    (net (code "65") (name "unconnected-(U9-NC-Pad16)") (class "Default")
      (node (ref "U9") (pin "16") (pinfunction "NC_16") (pintype "passive+no_connect"))
    )
    (net (code "66") (name "unconnected-(U18-N1-Pad1)") (class "Default")
      (node (ref "U18") (pin "1") (pinfunction "N1_1") (pintype "passive+no_connect"))
    )
    (net (code "67") (name "unconnected-(U18-N2-Pad8)") (class "Default")
      (node (ref "U18") (pin "8") (pinfunction "N2_8") (pintype "passive+no_connect"))
    )
  )
)
